# rs-485-multiplier.net
KiCad netlist of a schematic drawn in EAGLE
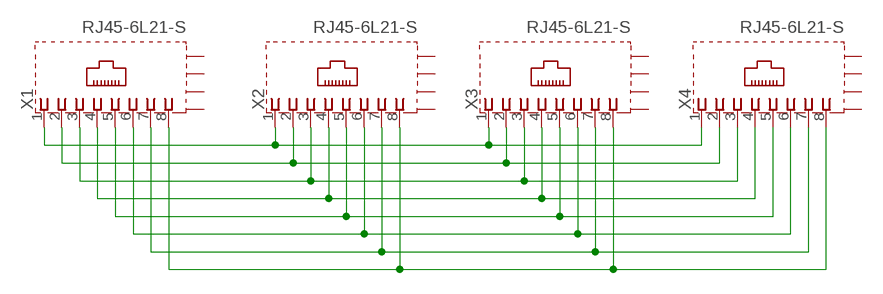
[diagram p0: schematic, sheet 1]

(export (version "E")
  (design (tool "Eeschema 10.0.6"))
  (components
    (comp (ref "X1")
      (value "RJ45-6L21-S")
      (footprint "eagle-import:RJ45-SHIELD1")
      (libsource (lib "eagle-import") (part "RJ4521-S-6L"))
    )
    (comp (ref "X2")
      (value "RJ45-6L21-S")
      (footprint "eagle-import:RJ45-SHIELD1")
      (libsource (lib "eagle-import") (part "RJ4521-S-6L"))
    )
    (comp (ref "X3")
      (value "RJ45-6L21-S")
      (footprint "eagle-import:RJ45-SHIELD1")
      (libsource (lib "eagle-import") (part "RJ4521-S-6L"))
    )
    (comp (ref "X4")
      (value "RJ45-6L21-S")
      (footprint "eagle-import:RJ45-SHIELD1")
      (libsource (lib "eagle-import") (part "RJ4521-S-6L"))
    )
  )
  (nets
    (net (code "1") (name "Net-(X1-Pad1)") (class "Default")
      (node (ref "X1") (pin "1") (pinfunction "1_1") (pintype "passive"))
      (node (ref "X2") (pin "1") (pinfunction "1_1") (pintype "passive"))
      (node (ref "X3") (pin "1") (pinfunction "1_1") (pintype "passive"))
      (node (ref "X4") (pin "1") (pinfunction "1_1") (pintype "passive"))
    )
    (net (code "2") (name "Net-(X1-Pad2)") (class "Default")
      (node (ref "X1") (pin "2") (pinfunction "2_2") (pintype "passive"))
      (node (ref "X2") (pin "2") (pinfunction "2_2") (pintype "passive"))
      (node (ref "X3") (pin "2") (pinfunction "2_2") (pintype "passive"))
      (node (ref "X4") (pin "2") (pinfunction "2_2") (pintype "passive"))
    )
    (net (code "3") (name "Net-(X1-Pad3)") (class "Default")
      (node (ref "X1") (pin "3") (pinfunction "3_3") (pintype "passive"))
      (node (ref "X2") (pin "3") (pinfunction "3_3") (pintype "passive"))
      (node (ref "X3") (pin "3") (pinfunction "3_3") (pintype "passive"))
      (node (ref "X4") (pin "3") (pinfunction "3_3") (pintype "passive"))
    )
    (net (code "4") (name "Net-(X1-Pad4)") (class "Default")
      (node (ref "X1") (pin "4") (pinfunction "4_4") (pintype "passive"))
      (node (ref "X2") (pin "4") (pinfunction "4_4") (pintype "passive"))
      (node (ref "X3") (pin "4") (pinfunction "4_4") (pintype "passive"))
      (node (ref "X4") (pin "4") (pinfunction "4_4") (pintype "passive"))
    )
    (net (code "5") (name "Net-(X1-Pad5)") (class "Default")
      (node (ref "X1") (pin "5") (pinfunction "5_5") (pintype "passive"))
      (node (ref "X2") (pin "5") (pinfunction "5_5") (pintype "passive"))
      (node (ref "X3") (pin "5") (pinfunction "5_5") (pintype "passive"))
      (node (ref "X4") (pin "5") (pinfunction "5_5") (pintype "passive"))
    )
    (net (code "6") (name "Net-(X1-Pad6)") (class "Default")
      (node (ref "X1") (pin "6") (pinfunction "6_6") (pintype "passive"))
      (node (ref "X2") (pin "6") (pinfunction "6_6") (pintype "passive"))
      (node (ref "X3") (pin "6") (pinfunction "6_6") (pintype "passive"))
      (node (ref "X4") (pin "6") (pinfunction "6_6") (pintype "passive"))
    )
    (net (code "7") (name "Net-(X1-Pad7)") (class "Default")
      (node (ref "X1") (pin "7") (pinfunction "7_7") (pintype "passive"))
      (node (ref "X2") (pin "7") (pinfunction "7_7") (pintype "passive"))
      (node (ref "X3") (pin "7") (pinfunction "7_7") (pintype "passive"))
      (node (ref "X4") (pin "7") (pinfunction "7_7") (pintype "passive"))
    )
    (net (code "8") (name "Net-(X1-Pad8)") (class "Default")
      (node (ref "X1") (pin "8") (pinfunction "8_8") (pintype "passive"))
      (node (ref "X2") (pin "8") (pinfunction "8_8") (pintype "passive"))
      (node (ref "X3") (pin "8") (pinfunction "8_8") (pintype "passive"))
      (node (ref "X4") (pin "8") (pinfunction "8_8") (pintype "passive"))
    )
    (net (code "9") (name "unconnected-(X1-S-PadS1)") (class "Default")
      (node (ref "X1") (pin "S1") (pinfunction "S_S1") (pintype "passive"))
    )
    (net (code "10") (name "unconnected-(X1-S-PadS2)") (class "Default")
      (node (ref "X1") (pin "S2") (pinfunction "S_S2") (pintype "passive"))
    )
    (net (code "11") (name "unconnected-(X1-S-PadS3)") (class "Default")
      (node (ref "X1") (pin "S3") (pinfunction "S_S3") (pintype "passive"))
    )
    (net (code "12") (name "unconnected-(X1-S-PadS4)") (class "Default")
      (node (ref "X1") (pin "S4") (pinfunction "S_S4") (pintype "passive"))
    )
    (net (code "13") (name "unconnected-(X2-S-PadS1)") (class "Default")
      (node (ref "X2") (pin "S1") (pinfunction "S_S1") (pintype "passive"))
    )
    (net (code "14") (name "unconnected-(X2-S-PadS2)") (class "Default")
      (node (ref "X2") (pin "S2") (pinfunction "S_S2") (pintype "passive"))
    )
    (net (code "15") (name "unconnected-(X2-S-PadS3)") (class "Default")
      (node (ref "X2") (pin "S3") (pinfunction "S_S3") (pintype "passive"))
    )
    (net (code "16") (name "unconnected-(X2-S-PadS4)") (class "Default")
      (node (ref "X2") (pin "S4") (pinfunction "S_S4") (pintype "passive"))
    )
    (net (code "17") (name "unconnected-(X3-S-PadS1)") (class "Default")
      (node (ref "X3") (pin "S1") (pinfunction "S_S1") (pintype "passive"))
    )
    (net (code "18") (name "unconnected-(X3-S-PadS2)") (class "Default")
      (node (ref "X3") (pin "S2") (pinfunction "S_S2") (pintype "passive"))
    )
    (net (code "19") (name "unconnected-(X3-S-PadS3)") (class "Default")
      (node (ref "X3") (pin "S3") (pinfunction "S_S3") (pintype "passive"))
    )
    (net (code "20") (name "unconnected-(X3-S-PadS4)") (class "Default")
      (node (ref "X3") (pin "S4") (pinfunction "S_S4") (pintype "passive"))
    )
    (net (code "21") (name "unconnected-(X4-S-PadS1)") (class "Default")
      (node (ref "X4") (pin "S1") (pinfunction "S_S1") (pintype "passive"))
    )
    (net (code "22") (name "unconnected-(X4-S-PadS2)") (class "Default")
      (node (ref "X4") (pin "S2") (pinfunction "S_S2") (pintype "passive"))
    )
    (net (code "23") (name "unconnected-(X4-S-PadS3)") (class "Default")
      (node (ref "X4") (pin "S3") (pinfunction "S_S3") (pintype "passive"))
    )
    (net (code "24") (name "unconnected-(X4-S-PadS4)") (class "Default")
      (node (ref "X4") (pin "S4") (pinfunction "S_S4") (pintype "passive"))
    )
  )
)
